# ArduBerry_3_0.net
KiCad netlist of a schematic drawn in EAGLE
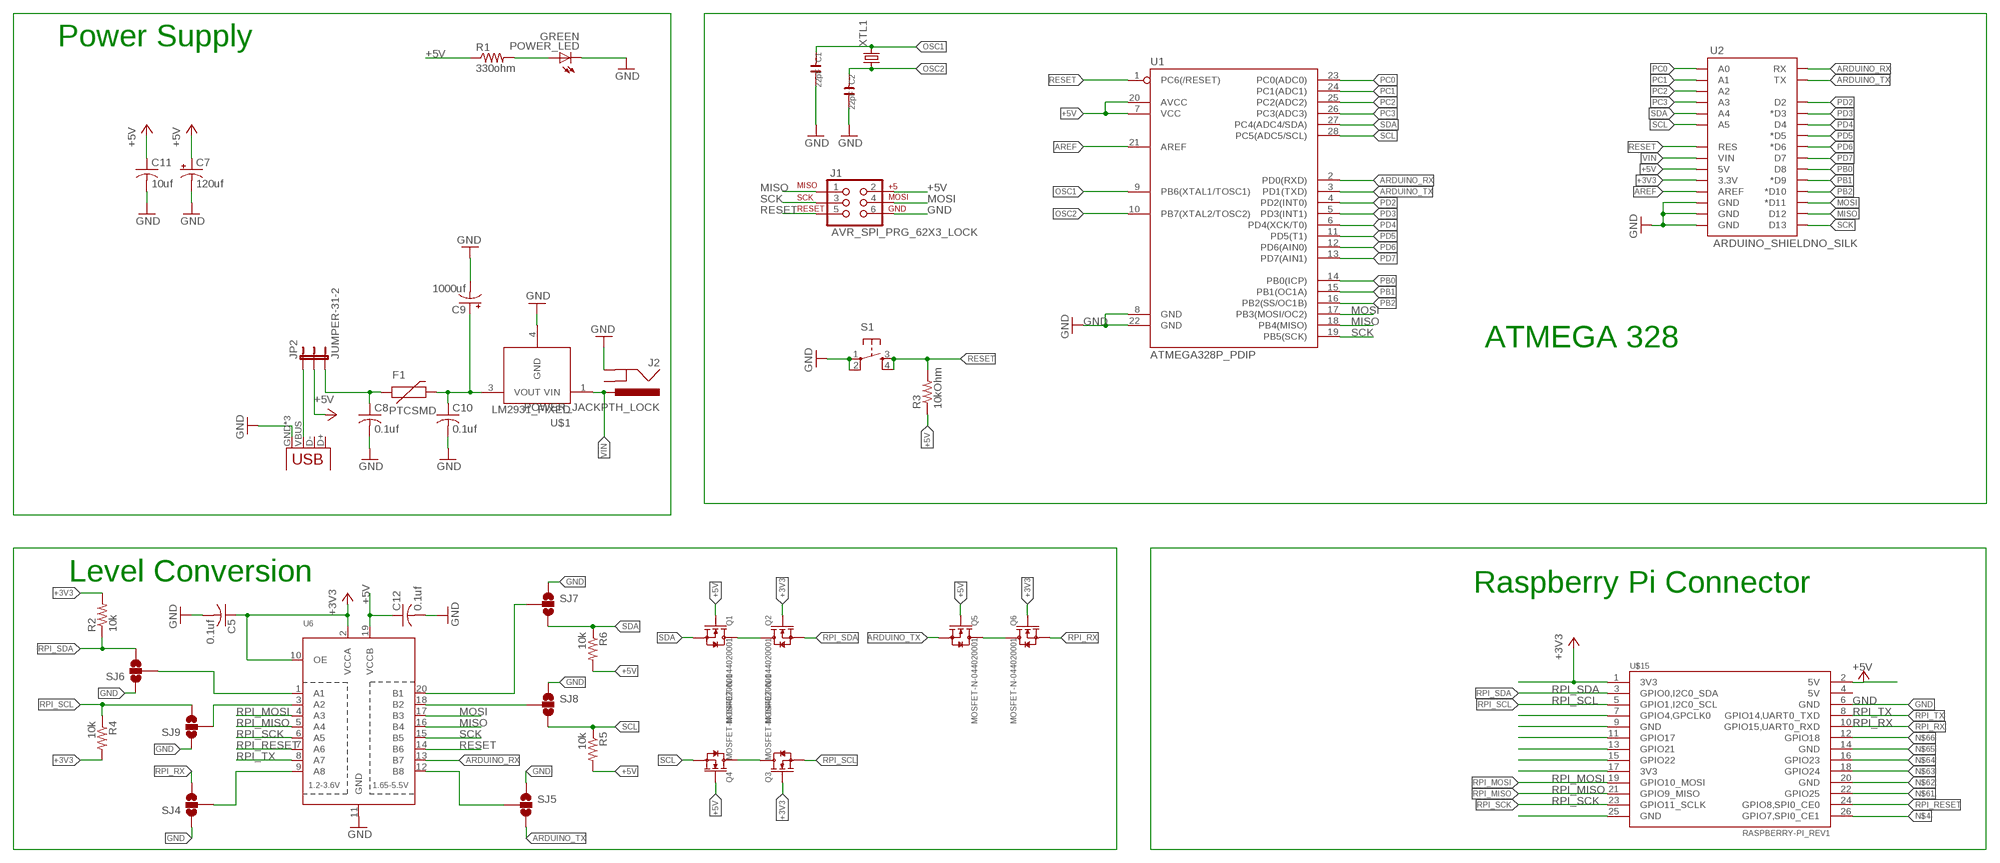
[diagram p0: schematic, sheet 1]

(export (version "E")
  (design (tool "Eeschema 10.0.6"))
  (components
    (comp (ref "C1")
      (value "22pF")
      (footprint "eagle-import:C0805")
      (libsource (lib "eagle-import") (part "C-0805"))
    )
    (comp (ref "C2")
      (value "22pF")
      (footprint "eagle-import:C0805")
      (libsource (lib "eagle-import") (part "C-0805"))
    )
    (comp (ref "C5")
      (value "0.1uf")
      (footprint "eagle-import:C0603")
      (libsource (lib "eagle-import") (part "resistor_C-USC0603"))
    )
    (comp (ref "C7")
      (value "120uf")
      (footprint "eagle-import:E2,5-6")
      (libsource (lib "eagle-import") (part "CPOL-USE2.5-6"))
    )
    (comp (ref "C8")
      (value "0.1uf")
      (footprint "eagle-import:C0603")
      (libsource (lib "eagle-import") (part "resistor_C-USC0603"))
    )
    (comp (ref "C9")
      (value "1000uf")
      (footprint "eagle-import:E3,5-10")
      (libsource (lib "eagle-import") (part "CPOL-USE3.5-10"))
    )
    (comp (ref "C10")
      (value "0.1uf")
      (footprint "eagle-import:C0603")
      (libsource (lib "eagle-import") (part "resistor_C-USC0603"))
    )
    (comp (ref "C11")
      (value "10uf")
      (footprint "eagle-import:C0805")
      (libsource (lib "eagle-import") (part "C-USC0805"))
    )
    (comp (ref "C12")
      (value "0.1uf")
      (footprint "eagle-import:C0603")
      (libsource (lib "eagle-import") (part "resistor_C-USC0603"))
    )
    (comp (ref "F1")
      (value "PTCSMD")
      (footprint "eagle-import:PTC-1206")
      (libsource (lib "eagle-import") (part "PTCSMD"))
    )
    (comp (ref "J1")
      (value "AVR_SPI_PRG_62X3_LOCK")
      (footprint "eagle-import:2X3_LOCK")
      (libsource (lib "eagle-import") (part "AVR_SPI_PRG_62X3_LOCK"))
    )
    (comp (ref "J2")
      (value "POWER_JACKPTH_LOCK")
      (footprint "eagle-import:POWER_JACK_PTH_LOCK")
      (libsource (lib "eagle-import") (part "POWER_JACKPTH_LOCK"))
    )
    (comp (ref "JP1")
      (value "USB-MICROB")
      (footprint "eagle-import:USB-MICROB")
      (libsource (lib "eagle-import") (part "USB-MICROB"))
    )
    (comp (ref "JP2")
      (value "JUMPER-31-2")
      (footprint "eagle-import:SJ_3_PASTE1&2")
      (libsource (lib "eagle-import") (part "JUMPER-31-2"))
    )
    (comp (ref "POWER_LED")
      (value "GREEN")
      (footprint "eagle-import:LED-0603")
      (libsource (lib "eagle-import") (part "LED-GREEN0603"))
    )
    (comp (ref "Q1")
      (value "MOSFET-N-044020001")
      (footprint "eagle-import:SOT23")
      (libsource (lib "eagle-import") (part "MOSFET-N-044020001"))
    )
    (comp (ref "Q2")
      (value "MOSFET-N-044020001")
      (footprint "eagle-import:SOT23")
      (libsource (lib "eagle-import") (part "MOSFET-N-044020001"))
    )
    (comp (ref "Q3")
      (value "MOSFET-N-044020001")
      (footprint "eagle-import:SOT23")
      (libsource (lib "eagle-import") (part "MOSFET-N-044020001"))
    )
    (comp (ref "Q4")
      (value "MOSFET-N-044020001")
      (footprint "eagle-import:SOT23")
      (libsource (lib "eagle-import") (part "MOSFET-N-044020001"))
    )
    (comp (ref "Q5")
      (value "MOSFET-N-044020001")
      (footprint "eagle-import:SOT23")
      (libsource (lib "eagle-import") (part "MOSFET-N-044020001"))
    )
    (comp (ref "Q6")
      (value "MOSFET-N-044020001")
      (footprint "eagle-import:SOT23")
      (libsource (lib "eagle-import") (part "MOSFET-N-044020001"))
    )
    (comp (ref "R1")
      (value "330ohm")
      (footprint "eagle-import:0603-RES")
      (libsource (lib "eagle-import") (part "RESISTOR0603"))
    )
    (comp (ref "R2")
      (value "10k")
      (footprint "eagle-import:0603-RES")
      (libsource (lib "eagle-import") (part "RESISTOR0603"))
    )
    (comp (ref "R3")
      (value "10kOhm")
      (footprint "eagle-import:0603-RES")
      (libsource (lib "eagle-import") (part "RESISTOR0603"))
    )
    (comp (ref "R4")
      (value "10k")
      (footprint "eagle-import:0603-RES")
      (libsource (lib "eagle-import") (part "RESISTOR0603"))
    )
    (comp (ref "R5")
      (value "10k")
      (footprint "eagle-import:0603-RES")
      (libsource (lib "eagle-import") (part "RESISTOR0603"))
    )
    (comp (ref "R6")
      (value "10k")
      (footprint "eagle-import:0603-RES")
      (libsource (lib "eagle-import") (part "RESISTOR0603"))
    )
    (comp (ref "S1")
      (value "TAC_SWITCHSMD")
      (footprint "eagle-import:TACTILE_SWITCH_SMD")
      (libsource (lib "eagle-import") (part "TAC_SWITCHSMD"))
    )
    (comp (ref "SJ4")
      (value "SOLDERJUMPER_2WAYPASTE1&2")
      (footprint "eagle-import:SJ_3_PASTE1&2")
      (libsource (lib "eagle-import") (part "SOLDERJUMPER_2WAYPASTE1&2"))
    )
    (comp (ref "SJ5")
      (value "SOLDERJUMPER_2WAYPASTE1&2")
      (footprint "eagle-import:SJ_3_PASTE1&2")
      (libsource (lib "eagle-import") (part "SOLDERJUMPER_2WAYPASTE1&2"))
    )
    (comp (ref "SJ6")
      (value "SOLDERJUMPER_2WAYPASTE1&2")
      (footprint "eagle-import:SJ_3_PASTE1&2")
      (libsource (lib "eagle-import") (part "SOLDERJUMPER_2WAYPASTE1&2"))
    )
    (comp (ref "SJ7")
      (value "SOLDERJUMPER_2WAYPASTE1&2")
      (footprint "eagle-import:SJ_3_PASTE1&2")
      (libsource (lib "eagle-import") (part "SOLDERJUMPER_2WAYPASTE1&2"))
    )
    (comp (ref "SJ8")
      (value "SOLDERJUMPER_2WAYPASTE1&2")
      (footprint "eagle-import:SJ_3_PASTE1&2")
      (libsource (lib "eagle-import") (part "SOLDERJUMPER_2WAYPASTE1&2"))
    )
    (comp (ref "SJ9")
      (value "SOLDERJUMPER_2WAYPASTE1&2")
      (footprint "eagle-import:SJ_3_PASTE1&2")
      (libsource (lib "eagle-import") (part "SOLDERJUMPER_2WAYPASTE1&2"))
    )
    (comp (ref "U$1")
      (value "LM2931_FIXED")
      (footprint "eagle-import:DPAK")
      (libsource (lib "eagle-import") (part "LM2931_FIXED"))
    )
    (comp (ref "U$15")
      (value "RASPBERRY-PI_REV1")
      (footprint "eagle-import:RASPBERRY-PI_REV1")
      (libsource (lib "eagle-import") (part "RASPBERRY-PI_REV1"))
    )
    (comp (ref "U1")
      (value "ATMEGA328P_PDIP")
      (footprint "eagle-import:DIL28-3")
      (libsource (lib "eagle-import") (part "ATMEGA328P_PDIP"))
    )
    (comp (ref "U2")
      (value "ARDUINO_SHIELDNO_SILK")
      (footprint "eagle-import:DUEMILANOVE_VIAS")
      (libsource (lib "eagle-import") (part "ARDUINO_SHIELDNO_SILK"))
    )
    (comp (ref "U6")
      (value "TXB0108PWR")
      (footprint "eagle-import:TSSOP20")
      (libsource (lib "eagle-import") (part "TXB0108PWR"))
    )
    (comp (ref "XTL1")
      (value "CRYSTALHC49S")
      (footprint "eagle-import:HC49_S")
      (libsource (lib "eagle-import") (part "CRYSTALHC49S"))
    )
  )
  (nets
    (net (code "1") (name "+3V3") (class "Default")
      (node (ref "C5") (pin "1") (pinfunction "1_1") (pintype "passive"))
      (node (ref "Q2") (pin "1") (pinfunction "G_1") (pintype "passive"))
      (node (ref "Q3") (pin "1") (pinfunction "G_1") (pintype "passive"))
      (node (ref "Q6") (pin "1") (pinfunction "G_1") (pintype "passive"))
      (node (ref "R2") (pin "2") (pinfunction "2_2") (pintype "passive"))
      (node (ref "R4") (pin "2") (pinfunction "2_2") (pintype "passive"))
      (node (ref "U$15") (pin "1") (pinfunction "3V3_1") (pintype "bidirectional"))
      (node (ref "U2") (pin "3.3V") (pinfunction "3.3V_3.3V") (pintype "bidirectional"))
      (node (ref "U6") (pin "10") (pinfunction "OE_10") (pintype "bidirectional"))
      (node (ref "U6") (pin "2") (pinfunction "VCCA_2") (pintype "bidirectional"))
    )
    (net (code "2") (name "+5V") (class "Default")
      (node (ref "C11") (pin "1") (pinfunction "1_1") (pintype "passive"))
      (node (ref "C12") (pin "1") (pinfunction "1_1") (pintype "passive"))
      (node (ref "C7") (pin "+") (pinfunction "+_+") (pintype "passive"))
      (node (ref "J1") (pin "2") (pinfunction "2_2") (pintype "passive"))
      (node (ref "JP2") (pin "2") (pinfunction "2_2") (pintype "passive"))
      (node (ref "Q1") (pin "1") (pinfunction "G_1") (pintype "passive"))
      (node (ref "Q4") (pin "1") (pinfunction "G_1") (pintype "passive"))
      (node (ref "Q5") (pin "1") (pinfunction "G_1") (pintype "passive"))
      (node (ref "R1") (pin "1") (pinfunction "1_1") (pintype "passive"))
      (node (ref "R3") (pin "1") (pinfunction "1_1") (pintype "passive"))
      (node (ref "R5") (pin "2") (pinfunction "2_2") (pintype "passive"))
      (node (ref "R6") (pin "2") (pinfunction "2_2") (pintype "passive"))
      (node (ref "U$15") (pin "2") (pinfunction "5V_2") (pintype "bidirectional"))
      (node (ref "U1") (pin "20") (pinfunction "AVCC_20") (pintype "bidirectional"))
      (node (ref "U1") (pin "7") (pinfunction "VCC_7") (pintype "bidirectional"))
      (node (ref "U2") (pin "5V") (pinfunction "5V_5V") (pintype "bidirectional"))
      (node (ref "U6") (pin "19") (pinfunction "VCCB_19") (pintype "bidirectional"))
    )
    (net (code "3") (name "ARDUINO_RX") (class "Default")
      (node (ref "U1") (pin "2") (pinfunction "PD0(RXD)_2") (pintype "bidirectional"))
      (node (ref "U2") (pin "RX") (pinfunction "RX_RX") (pintype "bidirectional"))
      (node (ref "U6") (pin "13") (pinfunction "B7_13") (pintype "bidirectional"))
    )
    (net (code "4") (name "ARDUINO_TX") (class "Default")
      (node (ref "Q5") (pin "2") (pinfunction "S_2") (pintype "passive"))
      (node (ref "SJ5") (pin "3") (pinfunction "3_3") (pintype "passive"))
      (node (ref "U1") (pin "3") (pinfunction "PD1(TXD)_3") (pintype "bidirectional"))
      (node (ref "U2") (pin "TX") (pinfunction "TX_TX") (pintype "bidirectional"))
    )
    (net (code "5") (name "AREF") (class "Default")
      (node (ref "U1") (pin "21") (pinfunction "AREF_21") (pintype "bidirectional"))
      (node (ref "U2") (pin "AREF") (pinfunction "AREF_AREF") (pintype "bidirectional"))
    )
    (net (code "6") (name "GND") (class "Default")
      (node (ref "C1") (pin "2") (pinfunction "2_2") (pintype "bidirectional"))
      (node (ref "C10") (pin "2") (pinfunction "2_2") (pintype "passive"))
      (node (ref "C11") (pin "2") (pinfunction "2_2") (pintype "passive"))
      (node (ref "C12") (pin "2") (pinfunction "2_2") (pintype "passive"))
      (node (ref "C2") (pin "2") (pinfunction "2_2") (pintype "bidirectional"))
      (node (ref "C5") (pin "2") (pinfunction "2_2") (pintype "passive"))
      (node (ref "C7") (pin "-") (pinfunction "-_-") (pintype "passive"))
      (node (ref "C8") (pin "2") (pinfunction "2_2") (pintype "passive"))
      (node (ref "C9") (pin "-") (pinfunction "-_-") (pintype "passive"))
      (node (ref "J1") (pin "6") (pinfunction "6_6") (pintype "passive"))
      (node (ref "J2") (pin "GND") (pinfunction "GND_GND") (pintype "bidirectional"))
      (node (ref "JP1") (pin "GND") (pinfunction "GND_GND") (pintype "bidirectional"))
      (node (ref "JP1") (pin "MT1") (pinfunction "GND_MT1") (pintype "bidirectional"))
      (node (ref "JP1") (pin "MT2") (pinfunction "GND_MT2") (pintype "bidirectional"))
      (node (ref "POWER_LED") (pin "C") (pinfunction "C_C") (pintype "passive"))
      (node (ref "S1") (pin "1") (pinfunction "1_1") (pintype "passive"))
      (node (ref "S1") (pin "2") (pinfunction "2_2") (pintype "passive"))
      (node (ref "SJ4") (pin "1") (pinfunction "1_1") (pintype "passive"))
      (node (ref "SJ5") (pin "1") (pinfunction "1_1") (pintype "passive"))
      (node (ref "SJ6") (pin "1") (pinfunction "1_1") (pintype "passive"))
      (node (ref "SJ7") (pin "1") (pinfunction "1_1") (pintype "passive"))
      (node (ref "SJ8") (pin "1") (pinfunction "1_1") (pintype "passive"))
      (node (ref "SJ9") (pin "1") (pinfunction "1_1") (pintype "passive"))
      (node (ref "U$1") (pin "4") (pinfunction "GND_4") (pintype "bidirectional"))
      (node (ref "U$15") (pin "6") (pinfunction "GND_6") (pintype "bidirectional"))
      (node (ref "U1") (pin "22") (pinfunction "GND_22") (pintype "bidirectional"))
      (node (ref "U1") (pin "8") (pinfunction "GND_8") (pintype "bidirectional"))
      (node (ref "U2") (pin "GND@0") (pinfunction "GND_GND@0") (pintype "bidirectional"))
      (node (ref "U2") (pin "GND@1") (pinfunction "GND_GND@1") (pintype "bidirectional"))
      (node (ref "U2") (pin "GND@2") (pinfunction "GND_GND@2") (pintype "bidirectional"))
      (node (ref "U6") (pin "11") (pinfunction "GND_11") (pintype "bidirectional"))
    )
    (net (code "7") (name "MISO") (class "Default")
      (node (ref "J1") (pin "1") (pinfunction "1_1") (pintype "passive"))
      (node (ref "U1") (pin "18") (pinfunction "PB4(MISO)_18") (pintype "bidirectional"))
      (node (ref "U2") (pin "D12") (pinfunction "D12_D12") (pintype "bidirectional"))
      (node (ref "U6") (pin "16") (pinfunction "B4_16") (pintype "bidirectional"))
    )
    (net (code "8") (name "MOSI") (class "Default")
      (node (ref "J1") (pin "4") (pinfunction "4_4") (pintype "passive"))
      (node (ref "U1") (pin "17") (pinfunction "PB3(MOSI/OC2)_17") (pintype "bidirectional"))
      (node (ref "U2") (pin "D11") (pinfunction "*D11_D11") (pintype "bidirectional"))
      (node (ref "U6") (pin "17") (pinfunction "B3_17") (pintype "bidirectional"))
    )
    (net (code "9") (name "N$4") (class "Default")
      (node (ref "U$15") (pin "26") (pinfunction "GPIO7,SPI0_CE1_26") (pintype "bidirectional"))
    )
    (net (code "10") (name "N$61") (class "Default")
      (node (ref "U$15") (pin "22") (pinfunction "GPIO25_22") (pintype "bidirectional"))
    )
    (net (code "11") (name "N$62") (class "Default")
      (node (ref "U$15") (pin "20") (pinfunction "GND_20") (pintype "bidirectional"))
    )
    (net (code "12") (name "N$63") (class "Default")
      (node (ref "U$15") (pin "18") (pinfunction "GPIO24_18") (pintype "bidirectional"))
    )
    (net (code "13") (name "N$64") (class "Default")
      (node (ref "U$15") (pin "16") (pinfunction "GPIO23_16") (pintype "bidirectional"))
    )
    (net (code "14") (name "N$65") (class "Default")
      (node (ref "U$15") (pin "14") (pinfunction "GND_14") (pintype "bidirectional"))
    )
    (net (code "15") (name "N$66") (class "Default")
      (node (ref "U$15") (pin "12") (pinfunction "GPIO18_12") (pintype "bidirectional"))
    )
    (net (code "16") (name "Net-(C8-Pad1)") (class "Default")
      (node (ref "C8") (pin "1") (pinfunction "1_1") (pintype "passive"))
      (node (ref "F1") (pin "1") (pinfunction "1_1") (pintype "bidirectional"))
      (node (ref "JP2") (pin "3") (pinfunction "3_3") (pintype "passive"))
    )
    (net (code "17") (name "Net-(JP1-PadVBUS)") (class "Default")
      (node (ref "JP1") (pin "VBUS") (pinfunction "VBUS_VBUS") (pintype "bidirectional"))
      (node (ref "JP2") (pin "1") (pinfunction "1_1") (pintype "passive"))
    )
    (net (code "18") (name "Net-(POWER_LED-PadA)") (class "Default")
      (node (ref "POWER_LED") (pin "A") (pinfunction "A_A") (pintype "passive"))
      (node (ref "R1") (pin "2") (pinfunction "2_2") (pintype "passive"))
    )
    (net (code "19") (name "Net-(Q1-D)") (class "Default")
      (node (ref "Q1") (pin "3") (pinfunction "D_3") (pintype "passive"))
      (node (ref "Q2") (pin "3") (pinfunction "D_3") (pintype "passive"))
    )
    (net (code "20") (name "Net-(Q3-D)") (class "Default")
      (node (ref "Q3") (pin "3") (pinfunction "D_3") (pintype "passive"))
      (node (ref "Q4") (pin "3") (pinfunction "D_3") (pintype "passive"))
    )
    (net (code "21") (name "Net-(Q5-D)") (class "Default")
      (node (ref "Q5") (pin "3") (pinfunction "D_3") (pintype "passive"))
      (node (ref "Q6") (pin "3") (pinfunction "D_3") (pintype "passive"))
    )
    (net (code "22") (name "Net-(U$1-VOUT)") (class "Default")
      (node (ref "C10") (pin "1") (pinfunction "1_1") (pintype "passive"))
      (node (ref "C9") (pin "+") (pinfunction "+_+") (pintype "passive"))
      (node (ref "F1") (pin "2") (pinfunction "2_2") (pintype "bidirectional"))
      (node (ref "U$1") (pin "3") (pinfunction "VOUT_3") (pintype "bidirectional"))
    )
    (net (code "23") (name "Net-(U6-A1)") (class "Default")
      (node (ref "SJ6") (pin "2") (pinfunction "2_2") (pintype "passive"))
      (node (ref "U6") (pin "1") (pinfunction "A1_1") (pintype "bidirectional"))
    )
    (net (code "24") (name "Net-(U6-A2)") (class "Default")
      (node (ref "SJ9") (pin "2") (pinfunction "2_2") (pintype "passive"))
      (node (ref "U6") (pin "3") (pinfunction "A2_3") (pintype "bidirectional"))
    )
    (net (code "25") (name "Net-(U6-A8)") (class "Default")
      (node (ref "SJ4") (pin "2") (pinfunction "2_2") (pintype "passive"))
      (node (ref "U6") (pin "9") (pinfunction "A8_9") (pintype "bidirectional"))
    )
    (net (code "26") (name "Net-(U6-B1)") (class "Default")
      (node (ref "SJ7") (pin "2") (pinfunction "2_2") (pintype "passive"))
      (node (ref "U6") (pin "20") (pinfunction "B1_20") (pintype "bidirectional"))
    )
    (net (code "27") (name "Net-(U6-B2)") (class "Default")
      (node (ref "SJ8") (pin "2") (pinfunction "2_2") (pintype "passive"))
      (node (ref "U6") (pin "18") (pinfunction "B2_18") (pintype "bidirectional"))
    )
    (net (code "28") (name "Net-(U6-B8)") (class "Default")
      (node (ref "SJ5") (pin "2") (pinfunction "2_2") (pintype "passive"))
      (node (ref "U6") (pin "12") (pinfunction "B8_12") (pintype "bidirectional"))
    )
    (net (code "29") (name "OSC1") (class "Default")
      (node (ref "C1") (pin "1") (pinfunction "1_1") (pintype "bidirectional"))
      (node (ref "U1") (pin "9") (pinfunction "PB6(XTAL1/TOSC1)_9") (pintype "bidirectional"))
      (node (ref "XTL1") (pin "2") (pinfunction "2_2") (pintype "passive"))
    )
    (net (code "30") (name "OSC2") (class "Default")
      (node (ref "C2") (pin "1") (pinfunction "1_1") (pintype "bidirectional"))
      (node (ref "U1") (pin "10") (pinfunction "PB7(XTAL2/TOSC2)_10") (pintype "bidirectional"))
      (node (ref "XTL1") (pin "1") (pinfunction "1_1") (pintype "passive"))
    )
    (net (code "31") (name "PB0") (class "Default")
      (node (ref "U1") (pin "14") (pinfunction "PB0(ICP)_14") (pintype "bidirectional"))
      (node (ref "U2") (pin "D8") (pinfunction "D8_D8") (pintype "bidirectional"))
    )
    (net (code "32") (name "PB1") (class "Default")
      (node (ref "U1") (pin "15") (pinfunction "PB1(OC1A)_15") (pintype "bidirectional"))
      (node (ref "U2") (pin "D9") (pinfunction "*D9_D9") (pintype "bidirectional"))
    )
    (net (code "33") (name "PB2") (class "Default")
      (node (ref "U1") (pin "16") (pinfunction "PB2(SS/OC1B)_16") (pintype "bidirectional"))
      (node (ref "U2") (pin "D10") (pinfunction "*D10_D10") (pintype "bidirectional"))
    )
    (net (code "34") (name "PC0") (class "Default")
      (node (ref "U1") (pin "23") (pinfunction "PC0(ADC0)_23") (pintype "bidirectional"))
      (node (ref "U2") (pin "A0") (pinfunction "A0_A0") (pintype "bidirectional"))
    )
    (net (code "35") (name "PC1") (class "Default")
      (node (ref "U1") (pin "24") (pinfunction "PC1(ADC1)_24") (pintype "bidirectional"))
      (node (ref "U2") (pin "A1") (pinfunction "A1_A1") (pintype "bidirectional"))
    )
    (net (code "36") (name "PC2") (class "Default")
      (node (ref "U1") (pin "25") (pinfunction "PC2(ADC2)_25") (pintype "bidirectional"))
      (node (ref "U2") (pin "A2") (pinfunction "A2_A2") (pintype "bidirectional"))
    )
    (net (code "37") (name "PC3") (class "Default")
      (node (ref "U1") (pin "26") (pinfunction "PC3(ADC3)_26") (pintype "bidirectional"))
      (node (ref "U2") (pin "A3") (pinfunction "A3_A3") (pintype "bidirectional"))
    )
    (net (code "38") (name "PD2") (class "Default")
      (node (ref "U1") (pin "4") (pinfunction "PD2(INT0)_4") (pintype "bidirectional"))
      (node (ref "U2") (pin "D2") (pinfunction "D2_D2") (pintype "bidirectional"))
    )
    (net (code "39") (name "PD3") (class "Default")
      (node (ref "U1") (pin "5") (pinfunction "PD3(INT1)_5") (pintype "bidirectional"))
      (node (ref "U2") (pin "D3") (pinfunction "*D3_D3") (pintype "bidirectional"))
    )
    (net (code "40") (name "PD4") (class "Default")
      (node (ref "U1") (pin "6") (pinfunction "PD4(XCK/T0)_6") (pintype "bidirectional"))
      (node (ref "U2") (pin "D4") (pinfunction "D4_D4") (pintype "bidirectional"))
    )
    (net (code "41") (name "PD5") (class "Default")
      (node (ref "U1") (pin "11") (pinfunction "PD5(T1)_11") (pintype "bidirectional"))
      (node (ref "U2") (pin "D5") (pinfunction "*D5_D5") (pintype "bidirectional"))
    )
    (net (code "42") (name "PD6") (class "Default")
      (node (ref "U1") (pin "12") (pinfunction "PD6(AIN0)_12") (pintype "bidirectional"))
      (node (ref "U2") (pin "D6") (pinfunction "*D6_D6") (pintype "bidirectional"))
    )
    (net (code "43") (name "PD7") (class "Default")
      (node (ref "U1") (pin "13") (pinfunction "PD7(AIN1)_13") (pintype "bidirectional"))
      (node (ref "U2") (pin "D7") (pinfunction "D7_D7") (pintype "bidirectional"))
    )
    (net (code "44") (name "RESET") (class "Default")
      (node (ref "J1") (pin "5") (pinfunction "5_5") (pintype "passive"))
      (node (ref "R3") (pin "2") (pinfunction "2_2") (pintype "passive"))
      (node (ref "S1") (pin "3") (pinfunction "3_3") (pintype "passive"))
      (node (ref "S1") (pin "4") (pinfunction "4_4") (pintype "passive"))
      (node (ref "U1") (pin "1") (pinfunction "PC6(/RESET)_1") (pintype "bidirectional"))
      (node (ref "U2") (pin "RES") (pinfunction "RES_RES") (pintype "bidirectional"))
      (node (ref "U6") (pin "14") (pinfunction "B6_14") (pintype "bidirectional"))
    )
    (net (code "45") (name "RPI_MISO") (class "Default")
      (node (ref "U$15") (pin "21") (pinfunction "GPIO9_MISO_21") (pintype "bidirectional"))
      (node (ref "U6") (pin "5") (pinfunction "A4_5") (pintype "bidirectional"))
    )
    (net (code "46") (name "RPI_MOSI") (class "Default")
      (node (ref "U$15") (pin "19") (pinfunction "GPIO10_MOSI_19") (pintype "bidirectional"))
      (node (ref "U6") (pin "4") (pinfunction "A3_4") (pintype "bidirectional"))
    )
    (net (code "47") (name "RPI_RESET") (class "Default")
      (node (ref "U$15") (pin "24") (pinfunction "GPIO8,SPI0_CE0_24") (pintype "bidirectional"))
      (node (ref "U6") (pin "7") (pinfunction "A6_7") (pintype "bidirectional"))
    )
    (net (code "48") (name "RPI_RX") (class "Default")
      (node (ref "Q6") (pin "2") (pinfunction "S_2") (pintype "passive"))
      (node (ref "SJ4") (pin "3") (pinfunction "3_3") (pintype "passive"))
      (node (ref "U$15") (pin "10") (pinfunction "GPIO15,UART0_RXD_10") (pintype "bidirectional"))
    )
    (net (code "49") (name "RPI_SCK") (class "Default")
      (node (ref "U$15") (pin "23") (pinfunction "GPIO11_SCLK_23") (pintype "bidirectional"))
      (node (ref "U6") (pin "6") (pinfunction "A5_6") (pintype "bidirectional"))
    )
    (net (code "50") (name "RPI_SCL") (class "Default")
      (node (ref "Q3") (pin "2") (pinfunction "S_2") (pintype "passive"))
      (node (ref "R4") (pin "1") (pinfunction "1_1") (pintype "passive"))
      (node (ref "SJ9") (pin "3") (pinfunction "3_3") (pintype "passive"))
      (node (ref "U$15") (pin "5") (pinfunction "GPIO1,I2C0_SCL_5") (pintype "bidirectional"))
    )
    (net (code "51") (name "RPI_SDA") (class "Default")
      (node (ref "Q2") (pin "2") (pinfunction "S_2") (pintype "passive"))
      (node (ref "R2") (pin "1") (pinfunction "1_1") (pintype "passive"))
      (node (ref "SJ6") (pin "3") (pinfunction "3_3") (pintype "passive"))
      (node (ref "U$15") (pin "3") (pinfunction "GPIO0,I2C0_SDA_3") (pintype "bidirectional"))
    )
    (net (code "52") (name "RPI_TX") (class "Default")
      (node (ref "U$15") (pin "8") (pinfunction "GPIO14,UART0_TXD_8") (pintype "bidirectional"))
      (node (ref "U6") (pin "8") (pinfunction "A7_8") (pintype "bidirectional"))
    )
    (net (code "53") (name "SCK") (class "Default")
      (node (ref "J1") (pin "3") (pinfunction "3_3") (pintype "passive"))
      (node (ref "U1") (pin "19") (pinfunction "PB5(SCK)_19") (pintype "bidirectional"))
      (node (ref "U2") (pin "D13") (pinfunction "D13_D13") (pintype "bidirectional"))
      (node (ref "U6") (pin "15") (pinfunction "B5_15") (pintype "bidirectional"))
    )
    (net (code "54") (name "SCL") (class "Default")
      (node (ref "Q4") (pin "2") (pinfunction "S_2") (pintype "passive"))
      (node (ref "R5") (pin "1") (pinfunction "1_1") (pintype "passive"))
      (node (ref "SJ8") (pin "3") (pinfunction "3_3") (pintype "passive"))
      (node (ref "U1") (pin "28") (pinfunction "PC5(ADC5/SCL)_28") (pintype "bidirectional"))
      (node (ref "U2") (pin "A5") (pinfunction "A5_A5") (pintype "bidirectional"))
    )
    (net (code "55") (name "SDA") (class "Default")
      (node (ref "Q1") (pin "2") (pinfunction "S_2") (pintype "passive"))
      (node (ref "R6") (pin "1") (pinfunction "1_1") (pintype "passive"))
      (node (ref "SJ7") (pin "3") (pinfunction "3_3") (pintype "passive"))
      (node (ref "U1") (pin "27") (pinfunction "PC4(ADC4/SDA)_27") (pintype "bidirectional"))
      (node (ref "U2") (pin "A4") (pinfunction "A4_A4") (pintype "bidirectional"))
    )
    (net (code "56") (name "VIN") (class "Default")
      (node (ref "J2") (pin "PWR") (pinfunction "PWR_PWR") (pintype "bidirectional"))
      (node (ref "U$1") (pin "1") (pinfunction "VIN_1") (pintype "bidirectional"))
      (node (ref "U2") (pin "VIN") (pinfunction "VIN_VIN") (pintype "bidirectional"))
    )
    (net (code "57") (name "unconnected-(J2-PadGNDBREAK)") (class "Default")
      (node (ref "J2") (pin "GNDBREAK") (pinfunction "GNDBREAK_GNDBREAK") (pintype "bidirectional"))
    )
    (net (code "58") (name "unconnected-(JP1-PadD+)") (class "Default")
      (node (ref "JP1") (pin "D+") (pinfunction "D+_D+") (pintype "bidirectional"))
    )
    (net (code "59") (name "unconnected-(JP1-PadD-)") (class "Default")
      (node (ref "JP1") (pin "D-") (pinfunction "D-_D-") (pintype "bidirectional"))
    )
    (net (code "60") (name "unconnected-(U$15-3V3-Pad17)") (class "Default")
      (node (ref "U$15") (pin "17") (pinfunction "3V3_17") (pintype "bidirectional"))
    )
    (net (code "61") (name "unconnected-(U$15-5V-Pad4)") (class "Default")
      (node (ref "U$15") (pin "4") (pinfunction "5V_4") (pintype "bidirectional"))
    )
    (net (code "62") (name "unconnected-(U$15-GND-Pad9)") (class "Default")
      (node (ref "U$15") (pin "9") (pinfunction "GND_9") (pintype "bidirectional"))
    )
    (net (code "63") (name "unconnected-(U$15-GND-Pad25)") (class "Default")
      (node (ref "U$15") (pin "25") (pinfunction "GND_25") (pintype "bidirectional"))
    )
    (net (code "64") (name "unconnected-(U$15-GPIO4,GPCLK0-Pad7)") (class "Default")
      (node (ref "U$15") (pin "7") (pinfunction "GPIO4,GPCLK0_7") (pintype "bidirectional"))
    )
    (net (code "65") (name "unconnected-(U$15-GPIO17-Pad11)") (class "Default")
      (node (ref "U$15") (pin "11") (pinfunction "GPIO17_11") (pintype "bidirectional"))
    )
    (net (code "66") (name "unconnected-(U$15-GPIO21-Pad13)") (class "Default")
      (node (ref "U$15") (pin "13") (pinfunction "GPIO21_13") (pintype "bidirectional"))
    )
    (net (code "67") (name "unconnected-(U$15-GPIO22-Pad15)") (class "Default")
      (node (ref "U$15") (pin "15") (pinfunction "GPIO22_15") (pintype "bidirectional"))
    )
  )
)
